# photon_at7020_2_rf_test_2.net
KiCad netlist of a schematic drawn in EAGLE
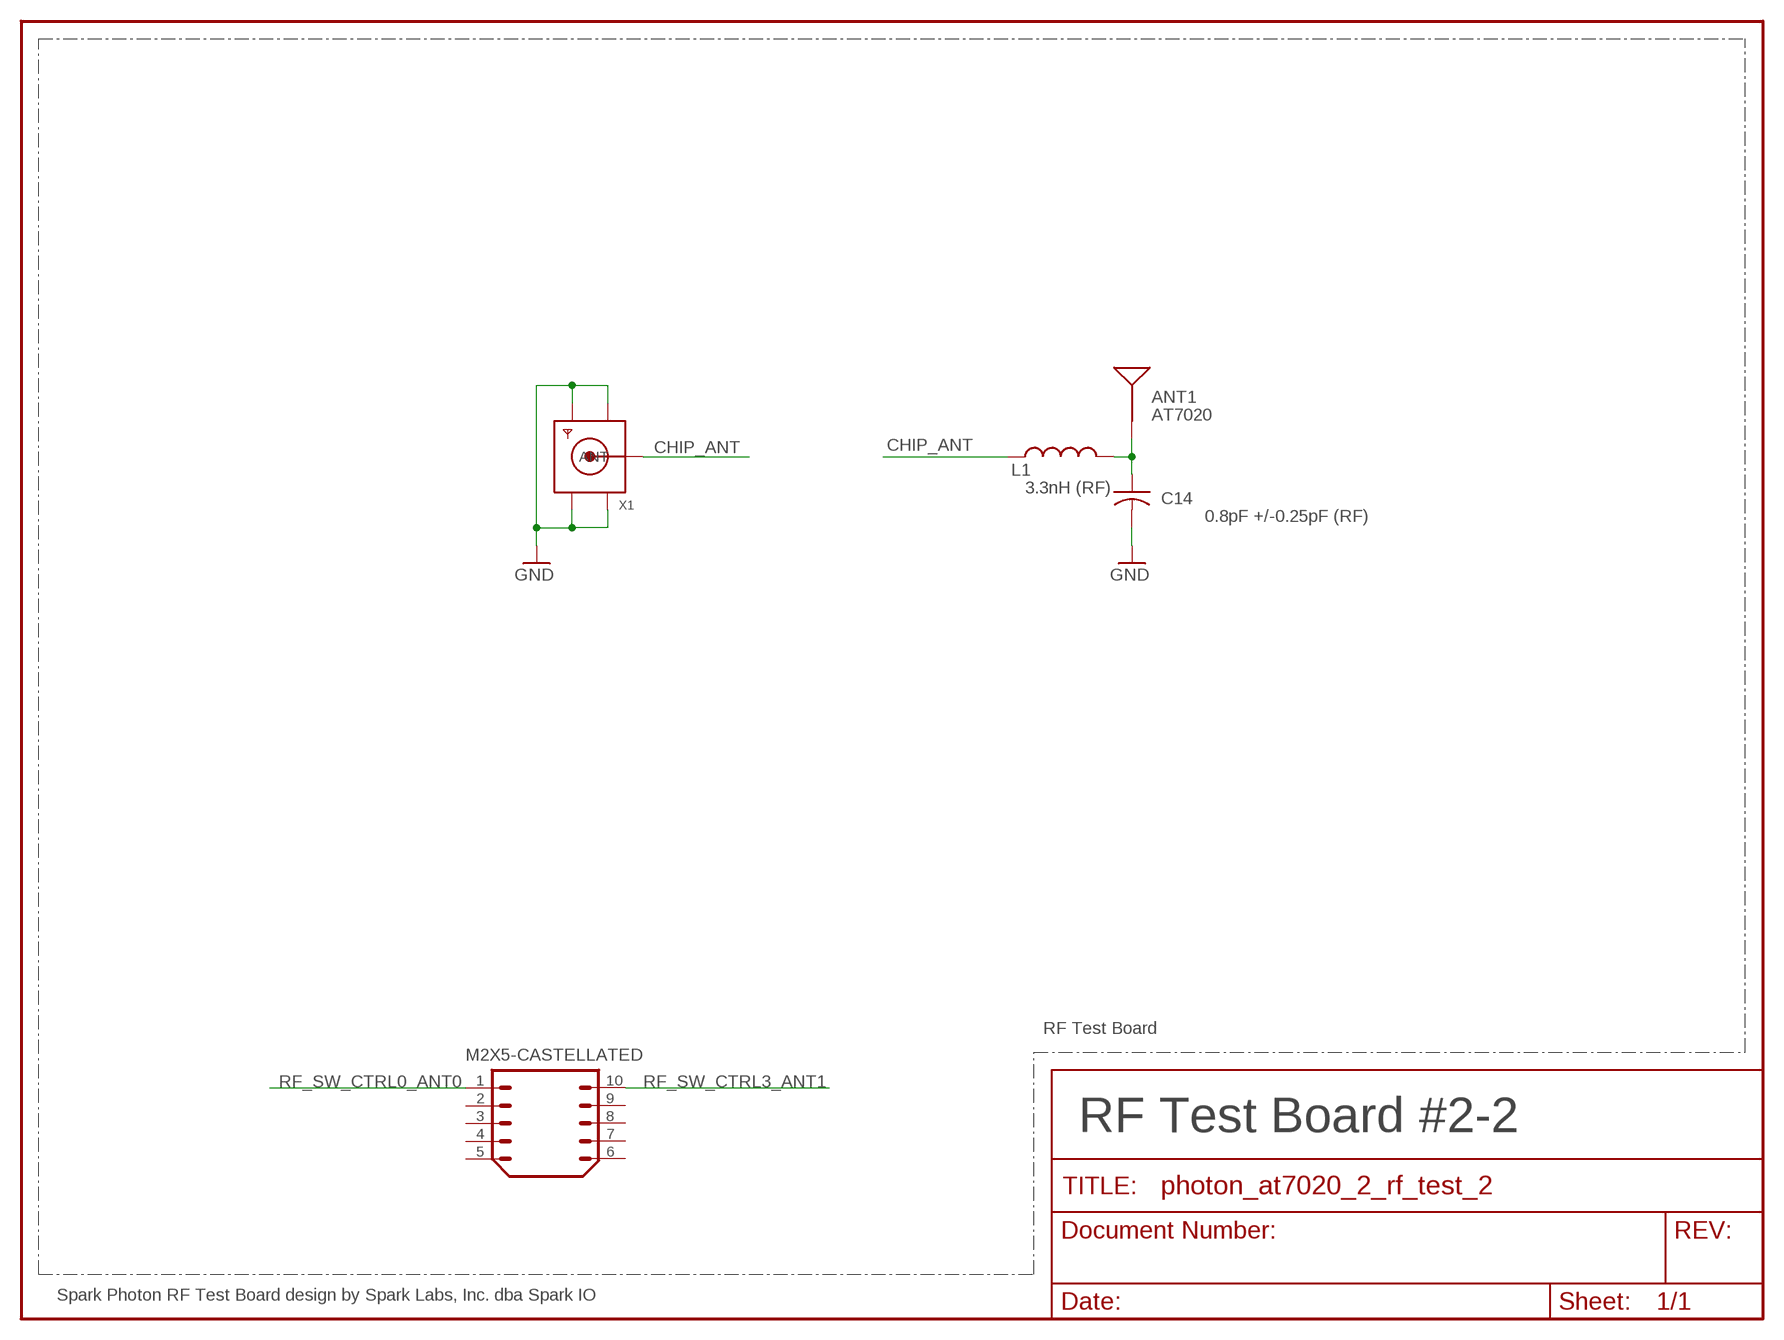
[diagram p0: schematic, sheet 1]

(export (version "E")
  (design (tool "Eeschema 10.0.6"))
  (components
    (comp (ref "ANT1")
      (value "AT7020")
      (footprint "eagle-import:AT7020")
      (libsource (lib "eagle-import") (part "AT7020"))
    )
    (comp (ref "C14")
      (value "0.8pF +/-0.25pF (RF)")
      (footprint "eagle-import:C0402_B")
      (libsource (lib "eagle-import") (part "C-US"))
    )
    (comp (ref "L1")
      (value "3.3nH (RF)")
      (footprint "eagle-import:L0402_B")
      (libsource (lib "eagle-import") (part "INDUCTOR"))
    )
    (comp (ref "M2X5-CASTELLATED")
      (value "M2X5")
      (footprint "eagle-import:2X5-CASTELLATED")
      (libsource (lib "eagle-import") (part "M2X5"))
    )
    (comp (ref "X1")
      (value "SMACONNECTOR_EDGE")
      (footprint "eagle-import:SMA_EDGELAUNCH")
      (libsource (lib "eagle-import") (part "SMACONNECTOR_EDGE"))
    )
  )
  (nets
    (net (code "1") (name "/CHIP_ANT") (class "Default")
      (node (ref "L1") (pin "1") (pinfunction "1_1") (pintype "passive"))
      (node (ref "X1") (pin "P") (pinfunction "ANT_P") (pintype "bidirectional"))
    )
    (net (code "2") (name "/RF_SW_CTRL0_ANT0") (class "Default")
      (node (ref "M2X5-CASTELLATED") (pin "1") (pinfunction "1_1") (pintype "passive"))
    )
    (net (code "3") (name "/RF_SW_CTRL3_ANT1") (class "Default")
      (node (ref "M2X5-CASTELLATED") (pin "10") (pinfunction "10_10") (pintype "passive"))
    )
    (net (code "4") (name "GND") (class "Default")
      (node (ref "C14") (pin "2") (pinfunction "2_2") (pintype "passive"))
      (node (ref "X1") (pin "GND@1") (pinfunction "GND4_GND@1") (pintype "power_in"))
      (node (ref "X1") (pin "GND@2") (pinfunction "GND3_GND@2") (pintype "power_in"))
      (node (ref "X1") (pin "GND@3") (pinfunction "GND2_GND@3") (pintype "power_in"))
      (node (ref "X1") (pin "GND@4") (pinfunction "GND1_GND@4") (pintype "power_in"))
    )
    (net (code "5") (name "Net-(ANT1-SIGNAL)") (class "Default")
      (node (ref "ANT1") (pin "1") (pinfunction "SIGNAL_1") (pintype "bidirectional"))
      (node (ref "C14") (pin "1") (pinfunction "1_1") (pintype "passive"))
      (node (ref "L1") (pin "2") (pinfunction "2_2") (pintype "passive"))
    )
    (net (code "6") (name "unconnected-(M2X5-CASTELLATED-Pad2)") (class "Default")
      (node (ref "M2X5-CASTELLATED") (pin "2") (pinfunction "2_2") (pintype "passive"))
    )
    (net (code "7") (name "unconnected-(M2X5-CASTELLATED-Pad3)") (class "Default")
      (node (ref "M2X5-CASTELLATED") (pin "3") (pinfunction "3_3") (pintype "passive"))
    )
    (net (code "8") (name "unconnected-(M2X5-CASTELLATED-Pad4)") (class "Default")
      (node (ref "M2X5-CASTELLATED") (pin "4") (pinfunction "4_4") (pintype "passive"))
    )
    (net (code "9") (name "unconnected-(M2X5-CASTELLATED-Pad5)") (class "Default")
      (node (ref "M2X5-CASTELLATED") (pin "5") (pinfunction "5_5") (pintype "passive"))
    )
    (net (code "10") (name "unconnected-(M2X5-CASTELLATED-Pad6)") (class "Default")
      (node (ref "M2X5-CASTELLATED") (pin "6") (pinfunction "6_6") (pintype "passive"))
    )
    (net (code "11") (name "unconnected-(M2X5-CASTELLATED-Pad7)") (class "Default")
      (node (ref "M2X5-CASTELLATED") (pin "7") (pinfunction "7_7") (pintype "passive"))
    )
    (net (code "12") (name "unconnected-(M2X5-CASTELLATED-Pad8)") (class "Default")
      (node (ref "M2X5-CASTELLATED") (pin "8") (pinfunction "8_8") (pintype "passive"))
    )
    (net (code "13") (name "unconnected-(M2X5-CASTELLATED-Pad9)") (class "Default")
      (node (ref "M2X5-CASTELLATED") (pin "9") (pinfunction "9_9") (pintype "passive"))
    )
  )
)
